# Gate_Driver_HV.net
KiCad netlist of a schematic drawn in Altium Designer
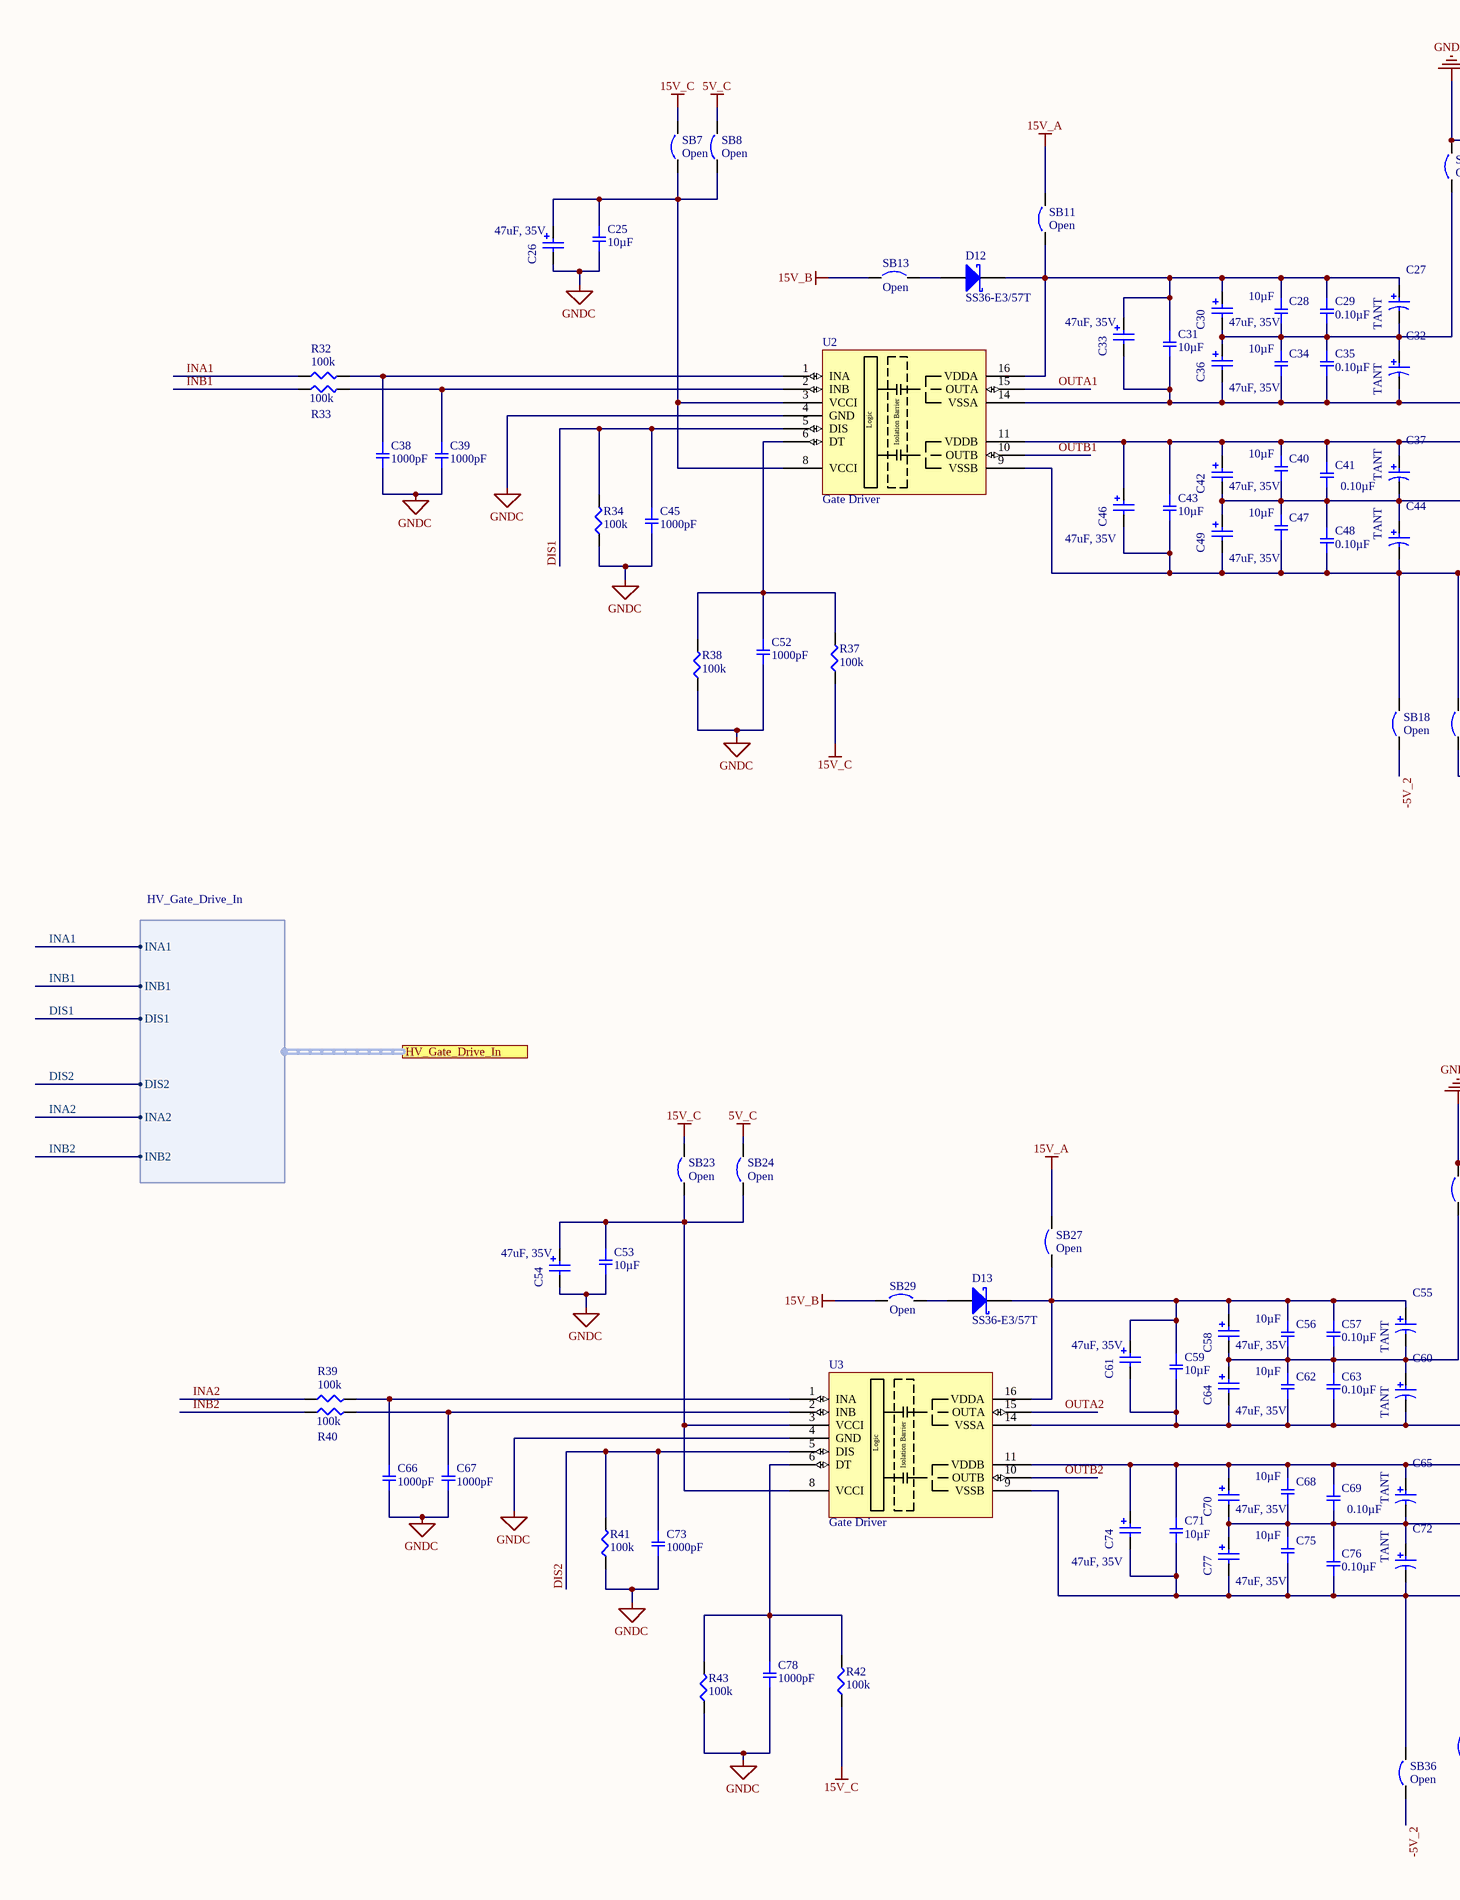
[diagram p0: Gate Driver HV.SchDoc, left]
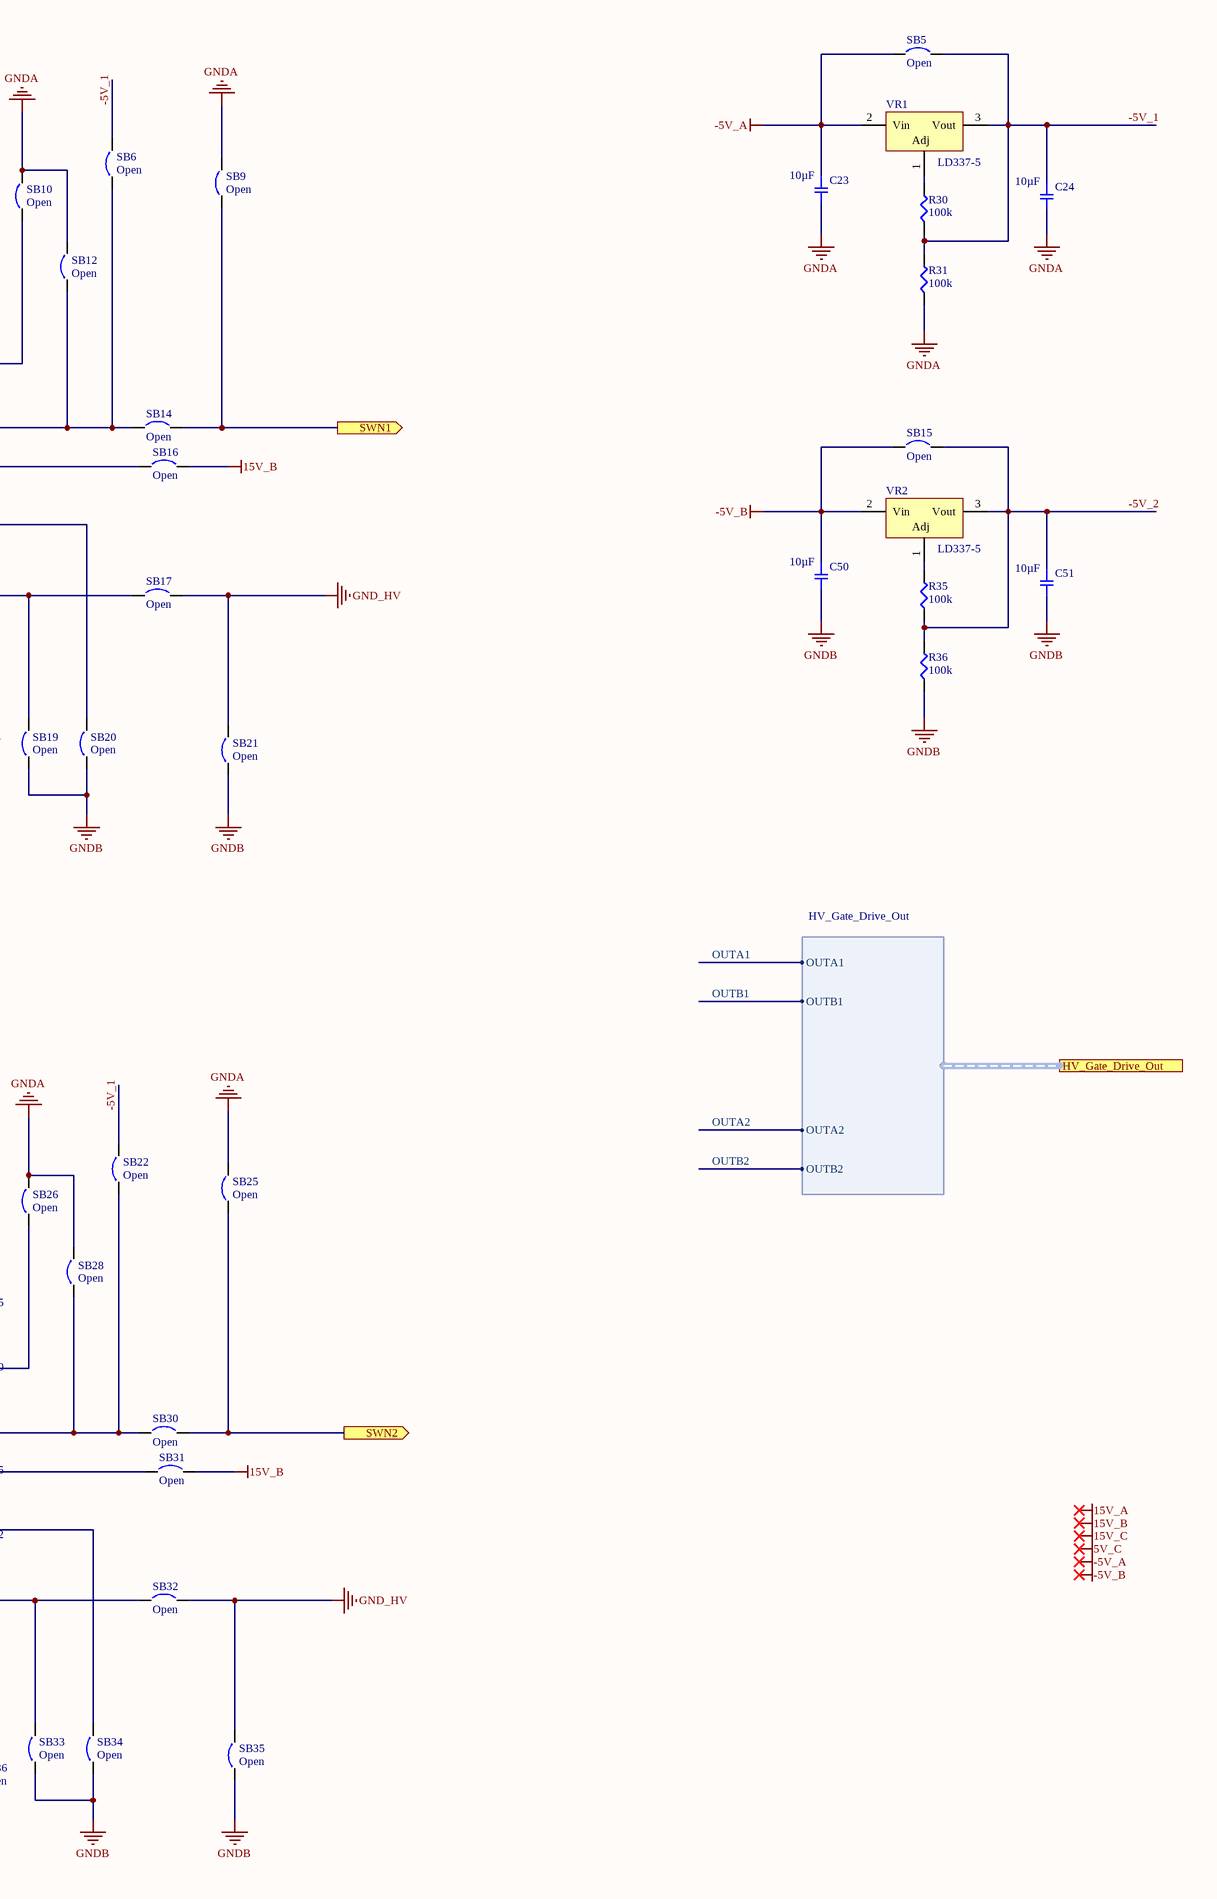
[diagram p1: Gate Driver HV.SchDoc, right]

(export (version "E")
  (design (tool "Eeschema 10.0.6"))
  (components
    (comp (ref "C23")
      (value "10µF")
      (footprint "SMD-1206C")
      (description "CAP CER 10UF 10V X7R 1206")
      (fields
        (field (name "DIGI-KEY PART NUMBER") "490-5848-1-ND")
        (field (name "PART NUMBER") "GCJ31CR71A106KA13L")
      )
      (libsource (lib "capacitor_murata_1206") (part "GCJ31CR71A106KA13L"))
    )
    (comp (ref "C24")
      (value "10µF")
      (footprint "SMD-1206C")
      (description "CAP CER 10UF 10V X7R 1206")
      (fields
        (field (name "DIGI-KEY PART NUMBER") "490-5848-1-ND")
        (field (name "PART NUMBER") "GCJ31CR71A106KA13L")
      )
      (libsource (lib "capacitor_murata_1206") (part "GCJ31CR71A106KA13L"))
    )
    (comp (ref "C25")
      (value "10µF")
      (footprint "SMD-1206C")
      (description "CAP CER 10UF 10V X7R 1206")
      (fields
        (field (name "DIGI-KEY PART NUMBER") "490-5848-1-ND")
        (field (name "PART NUMBER") "GCJ31CR71A106KA13L")
      )
      (libsource (lib "capacitor_murata_1206") (part "GCJ31CR71A106KA13L"))
    )
    (comp (ref "C26")
      (value "47uF, 35V")
      (footprint "WCAP-ASLL_6.3x5.5")
      (description "WCAP-ASLL SMT Aluminum Electrolytic Capacitors, D6.3mm x L5.5mm, 47uF, +/-20%, 35VDC")
      (fields (field (name "PART NUMBER") "865060543005") (field (name "PUBLISHER") "Wurth Elektronik"))
      (libsource (lib "Altium_WCAP-ASLL_SMD") (part "865060543005"))
    )
    (comp (ref "C27")
      (value "TANT")
      (footprint "KEMT-T491-D_L")
      (description "Tantalum Capacitor, 10 uF, +/- 10%, 35 V, -55 to 125 degC, 2-Pin SMD, RoHS, Tape and Reel")
      (fields (field (name "MANUFACTURER") "Kemet") (field (name "TOLERANCE") "20%"))
      (libsource (lib "Altium Content Vault") (part "CAP-P-2"))
    )
    (comp (ref "C28")
      (value "10µF")
      (footprint "SMD-1206C")
      (description "CAP CER 10UF 10V X7R 1206")
      (fields
        (field (name "DIGI-KEY PART NUMBER") "490-5848-1-ND")
        (field (name "PART NUMBER") "GCJ31CR71A106KA13L")
      )
      (libsource (lib "capacitor_murata_1206") (part "GCJ31CR71A106KA13L"))
    )
    (comp (ref "C29")
      (value "0.10µF")
      (footprint "SMD-1206C")
      (description "CAP CER 0.1UF 250V X7R 1206")
      (fields
        (field (name "DIGI-KEY PART NUMBER") "490-12647-1-ND")
        (field (name "PART NUMBER") "GCJ31CR72E104KXJ3L")
      )
      (libsource (lib "capacitor_murata_1206") (part "GCJ31CR72E104KXJ3L"))
    )
    (comp (ref "C30")
      (value "47uF, 35V")
      (footprint "WCAP-ASLL_6.3x5.5")
      (description "WCAP-ASLL SMT Aluminum Electrolytic Capacitors, D6.3mm x L5.5mm, 47uF, +/-20%, 35VDC")
      (fields (field (name "PART NUMBER") "865060543005") (field (name "PUBLISHER") "Wurth Elektronik"))
      (libsource (lib "Altium_WCAP-ASLL_SMD") (part "865060543005"))
    )
    (comp (ref "C31")
      (value "10µF")
      (footprint "SMD-1206C")
      (description "CAP CER 10UF 10V X7R 1206")
      (fields
        (field (name "DIGI-KEY PART NUMBER") "490-5848-1-ND")
        (field (name "PART NUMBER") "GCJ31CR71A106KA13L")
      )
      (libsource (lib "capacitor_murata_1206") (part "GCJ31CR71A106KA13L"))
    )
    (comp (ref "C32")
      (value "TANT")
      (footprint "KEMT-T491-D_L")
      (description "Tantalum Capacitor, 10 uF, +/- 10%, 35 V, -55 to 125 degC, 2-Pin SMD, RoHS, Tape and Reel")
      (fields (field (name "MANUFACTURER") "Kemet") (field (name "TOLERANCE") "20%"))
      (libsource (lib "Altium Content Vault") (part "CAP-P-2"))
    )
    (comp (ref "C33")
      (value "47uF, 35V")
      (footprint "WCAP-ASLL_6.3x5.5")
      (description "WCAP-ASLL SMT Aluminum Electrolytic Capacitors, D6.3mm x L5.5mm, 47uF, +/-20%, 35VDC")
      (fields (field (name "PART NUMBER") "865060543005") (field (name "PUBLISHER") "Wurth Elektronik"))
      (libsource (lib "Altium_WCAP-ASLL_SMD") (part "865060543005"))
    )
    (comp (ref "C34")
      (value "10µF")
      (footprint "SMD-1206C")
      (description "CAP CER 10UF 10V X7R 1206")
      (fields
        (field (name "DIGI-KEY PART NUMBER") "490-5848-1-ND")
        (field (name "PART NUMBER") "GCJ31CR71A106KA13L")
      )
      (libsource (lib "capacitor_murata_1206") (part "GCJ31CR71A106KA13L"))
    )
    (comp (ref "C35")
      (value "0.10µF")
      (footprint "SMD-1206C")
      (description "CAP CER 0.1UF 250V X7R 1206")
      (fields
        (field (name "DIGI-KEY PART NUMBER") "490-12647-1-ND")
        (field (name "PART NUMBER") "GCJ31CR72E104KXJ3L")
      )
      (libsource (lib "capacitor_murata_1206") (part "GCJ31CR72E104KXJ3L"))
    )
    (comp (ref "C36")
      (value "47uF, 35V")
      (footprint "WCAP-ASLL_6.3x5.5")
      (description "WCAP-ASLL SMT Aluminum Electrolytic Capacitors, D6.3mm x L5.5mm, 47uF, +/-20%, 35VDC")
      (fields (field (name "PART NUMBER") "865060543005") (field (name "PUBLISHER") "Wurth Elektronik"))
      (libsource (lib "Altium_WCAP-ASLL_SMD") (part "865060543005"))
    )
    (comp (ref "C37")
      (value "TANT")
      (footprint "KEMT-T491-D_L")
      (description "Tantalum Capacitor, 10 uF, +/- 10%, 35 V, -55 to 125 degC, 2-Pin SMD, RoHS, Tape and Reel")
      (fields (field (name "MANUFACTURER") "Kemet") (field (name "TOLERANCE") "20%"))
      (libsource (lib "Altium Content Vault") (part "CAP-P-2"))
    )
    (comp (ref "C38")
      (value "1000pF")
      (footprint "SMD-0805C")
      (description "CAP CER 1000PF 100V X7R 0805")
      (fields
        (field (name "DIGI-KEY PART NUMBER") "490-5818-1-ND")
        (field (name "PART NUMBER") "GCJ216R72A102KA01D")
      )
      (libsource (lib "capacitor_murata_0805") (part "GCJ216R72A102KA01D"))
    )
    (comp (ref "C39")
      (value "1000pF")
      (footprint "SMD-0805C")
      (description "CAP CER 1000PF 100V X7R 0805")
      (fields
        (field (name "DIGI-KEY PART NUMBER") "490-5818-1-ND")
        (field (name "PART NUMBER") "GCJ216R72A102KA01D")
      )
      (libsource (lib "capacitor_murata_0805") (part "GCJ216R72A102KA01D"))
    )
    (comp (ref "C40")
      (value "10µF")
      (footprint "SMD-1206C")
      (description "CAP CER 10UF 10V X7R 1206")
      (fields
        (field (name "DIGI-KEY PART NUMBER") "490-5848-1-ND")
        (field (name "PART NUMBER") "GCJ31CR71A106KA13L")
      )
      (libsource (lib "capacitor_murata_1206") (part "GCJ31CR71A106KA13L"))
    )
    (comp (ref "C41")
      (value "0.10µF")
      (footprint "SMD-1206C")
      (description "CAP CER 0.1UF 250V X7R 1206")
      (fields
        (field (name "DIGI-KEY PART NUMBER") "490-12647-1-ND")
        (field (name "PART NUMBER") "GCJ31CR72E104KXJ3L")
      )
      (libsource (lib "capacitor_murata_1206") (part "GCJ31CR72E104KXJ3L"))
    )
    (comp (ref "C42")
      (value "47uF, 35V")
      (footprint "WCAP-ASLL_6.3x5.5")
      (description "WCAP-ASLL SMT Aluminum Electrolytic Capacitors, D6.3mm x L5.5mm, 47uF, +/-20%, 35VDC")
      (fields (field (name "PART NUMBER") "865060543005") (field (name "PUBLISHER") "Wurth Elektronik"))
      (libsource (lib "Altium_WCAP-ASLL_SMD") (part "865060543005"))
    )
    (comp (ref "C43")
      (value "10µF")
      (footprint "SMD-1206C")
      (description "CAP CER 10UF 10V X7R 1206")
      (fields
        (field (name "DIGI-KEY PART NUMBER") "490-5848-1-ND")
        (field (name "PART NUMBER") "GCJ31CR71A106KA13L")
      )
      (libsource (lib "capacitor_murata_1206") (part "GCJ31CR71A106KA13L"))
    )
    (comp (ref "C44")
      (value "TANT")
      (footprint "KEMT-T491-D_L")
      (description "Tantalum Capacitor, 10 uF, +/- 10%, 35 V, -55 to 125 degC, 2-Pin SMD, RoHS, Tape and Reel")
      (fields (field (name "MANUFACTURER") "Kemet") (field (name "TOLERANCE") "20%"))
      (libsource (lib "Altium Content Vault") (part "CAP-P-2"))
    )
    (comp (ref "C45")
      (value "1000pF")
      (footprint "SMD-0805C")
      (description "CAP CER 1000PF 100V X7R 0805")
      (fields
        (field (name "DIGI-KEY PART NUMBER") "490-5818-1-ND")
        (field (name "PART NUMBER") "GCJ216R72A102KA01D")
      )
      (libsource (lib "capacitor_murata_0805") (part "GCJ216R72A102KA01D"))
    )
    (comp (ref "C46")
      (value "47uF, 35V")
      (footprint "WCAP-ASLL_6.3x5.5")
      (description "WCAP-ASLL SMT Aluminum Electrolytic Capacitors, D6.3mm x L5.5mm, 47uF, +/-20%, 35VDC")
      (fields (field (name "PART NUMBER") "865060543005") (field (name "PUBLISHER") "Wurth Elektronik"))
      (libsource (lib "Altium_WCAP-ASLL_SMD") (part "865060543005"))
    )
    (comp (ref "C47")
      (value "10µF")
      (footprint "SMD-1206C")
      (description "CAP CER 10UF 10V X7R 1206")
      (fields
        (field (name "DIGI-KEY PART NUMBER") "490-5848-1-ND")
        (field (name "PART NUMBER") "GCJ31CR71A106KA13L")
      )
      (libsource (lib "capacitor_murata_1206") (part "GCJ31CR71A106KA13L"))
    )
    (comp (ref "C48")
      (value "0.10µF")
      (footprint "SMD-1206C")
      (description "CAP CER 0.1UF 250V X7R 1206")
      (fields
        (field (name "DIGI-KEY PART NUMBER") "490-12647-1-ND")
        (field (name "PART NUMBER") "GCJ31CR72E104KXJ3L")
      )
      (libsource (lib "capacitor_murata_1206") (part "GCJ31CR72E104KXJ3L"))
    )
    (comp (ref "C49")
      (value "47uF, 35V")
      (footprint "WCAP-ASLL_6.3x5.5")
      (description "WCAP-ASLL SMT Aluminum Electrolytic Capacitors, D6.3mm x L5.5mm, 47uF, +/-20%, 35VDC")
      (fields (field (name "PART NUMBER") "865060543005") (field (name "PUBLISHER") "Wurth Elektronik"))
      (libsource (lib "Altium_WCAP-ASLL_SMD") (part "865060543005"))
    )
    (comp (ref "C50")
      (value "10µF")
      (footprint "SMD-1206C")
      (description "CAP CER 10UF 10V X7R 1206")
      (fields
        (field (name "DIGI-KEY PART NUMBER") "490-5848-1-ND")
        (field (name "PART NUMBER") "GCJ31CR71A106KA13L")
      )
      (libsource (lib "capacitor_murata_1206") (part "GCJ31CR71A106KA13L"))
    )
    (comp (ref "C51")
      (value "10µF")
      (footprint "SMD-1206C")
      (description "CAP CER 10UF 10V X7R 1206")
      (fields
        (field (name "DIGI-KEY PART NUMBER") "490-5848-1-ND")
        (field (name "PART NUMBER") "GCJ31CR71A106KA13L")
      )
      (libsource (lib "capacitor_murata_1206") (part "GCJ31CR71A106KA13L"))
    )
    (comp (ref "C52")
      (value "1000pF")
      (footprint "SMD-0805C")
      (description "CAP CER 1000PF 100V X7R 0805")
      (fields
        (field (name "DIGI-KEY PART NUMBER") "490-5818-1-ND")
        (field (name "PART NUMBER") "GCJ216R72A102KA01D")
      )
      (libsource (lib "capacitor_murata_0805") (part "GCJ216R72A102KA01D"))
    )
    (comp (ref "C53")
      (value "10µF")
      (footprint "SMD-1206C")
      (description "CAP CER 10UF 10V X7R 1206")
      (fields
        (field (name "DIGI-KEY PART NUMBER") "490-5848-1-ND")
        (field (name "PART NUMBER") "GCJ31CR71A106KA13L")
      )
      (libsource (lib "capacitor_murata_1206") (part "GCJ31CR71A106KA13L"))
    )
    (comp (ref "C54")
      (value "47uF, 35V")
      (footprint "WCAP-ASLL_6.3x5.5")
      (description "WCAP-ASLL SMT Aluminum Electrolytic Capacitors, D6.3mm x L5.5mm, 47uF, +/-20%, 35VDC")
      (fields (field (name "PART NUMBER") "865060543005") (field (name "PUBLISHER") "Wurth Elektronik"))
      (libsource (lib "Altium_WCAP-ASLL_SMD") (part "865060543005"))
    )
    (comp (ref "C55")
      (value "TANT")
      (footprint "KEMT-T491-D_L")
      (description "Tantalum Capacitor, 10 uF, +/- 10%, 35 V, -55 to 125 degC, 2-Pin SMD, RoHS, Tape and Reel")
      (fields (field (name "MANUFACTURER") "Kemet") (field (name "TOLERANCE") "20%"))
      (libsource (lib "Altium Content Vault") (part "CAP-P-2"))
    )
    (comp (ref "C56")
      (value "10µF")
      (footprint "SMD-1206C")
      (description "CAP CER 10UF 10V X7R 1206")
      (fields
        (field (name "DIGI-KEY PART NUMBER") "490-5848-1-ND")
        (field (name "PART NUMBER") "GCJ31CR71A106KA13L")
      )
      (libsource (lib "capacitor_murata_1206") (part "GCJ31CR71A106KA13L"))
    )
    (comp (ref "C57")
      (value "0.10µF")
      (footprint "SMD-1206C")
      (description "CAP CER 0.1UF 250V X7R 1206")
      (fields
        (field (name "DIGI-KEY PART NUMBER") "490-12647-1-ND")
        (field (name "PART NUMBER") "GCJ31CR72E104KXJ3L")
      )
      (libsource (lib "capacitor_murata_1206") (part "GCJ31CR72E104KXJ3L"))
    )
    (comp (ref "C58")
      (value "47uF, 35V")
      (footprint "WCAP-ASLL_6.3x5.5")
      (description "WCAP-ASLL SMT Aluminum Electrolytic Capacitors, D6.3mm x L5.5mm, 47uF, +/-20%, 35VDC")
      (fields (field (name "PART NUMBER") "865060543005") (field (name "PUBLISHER") "Wurth Elektronik"))
      (libsource (lib "Altium_WCAP-ASLL_SMD") (part "865060543005"))
    )
    (comp (ref "C59")
      (value "10µF")
      (footprint "SMD-1206C")
      (description "CAP CER 10UF 10V X7R 1206")
      (fields
        (field (name "DIGI-KEY PART NUMBER") "490-5848-1-ND")
        (field (name "PART NUMBER") "GCJ31CR71A106KA13L")
      )
      (libsource (lib "capacitor_murata_1206") (part "GCJ31CR71A106KA13L"))
    )
    (comp (ref "C60")
      (value "TANT")
      (footprint "KEMT-T491-D_L")
      (description "Tantalum Capacitor, 10 uF, +/- 10%, 35 V, -55 to 125 degC, 2-Pin SMD, RoHS, Tape and Reel")
      (fields (field (name "MANUFACTURER") "Kemet") (field (name "TOLERANCE") "20%"))
      (libsource (lib "Altium Content Vault") (part "CAP-P-2"))
    )
    (comp (ref "C61")
      (value "47uF, 35V")
      (footprint "WCAP-ASLL_6.3x5.5")
      (description "WCAP-ASLL SMT Aluminum Electrolytic Capacitors, D6.3mm x L5.5mm, 47uF, +/-20%, 35VDC")
      (fields (field (name "PART NUMBER") "865060543005") (field (name "PUBLISHER") "Wurth Elektronik"))
      (libsource (lib "Altium_WCAP-ASLL_SMD") (part "865060543005"))
    )
    (comp (ref "C62")
      (value "10µF")
      (footprint "SMD-1206C")
      (description "CAP CER 10UF 10V X7R 1206")
      (fields
        (field (name "DIGI-KEY PART NUMBER") "490-5848-1-ND")
        (field (name "PART NUMBER") "GCJ31CR71A106KA13L")
      )
      (libsource (lib "capacitor_murata_1206") (part "GCJ31CR71A106KA13L"))
    )
    (comp (ref "C63")
      (value "0.10µF")
      (footprint "SMD-1206C")
      (description "CAP CER 0.1UF 250V X7R 1206")
      (fields
        (field (name "DIGI-KEY PART NUMBER") "490-12647-1-ND")
        (field (name "PART NUMBER") "GCJ31CR72E104KXJ3L")
      )
      (libsource (lib "capacitor_murata_1206") (part "GCJ31CR72E104KXJ3L"))
    )
    (comp (ref "C64")
      (value "47uF, 35V")
      (footprint "WCAP-ASLL_6.3x5.5")
      (description "WCAP-ASLL SMT Aluminum Electrolytic Capacitors, D6.3mm x L5.5mm, 47uF, +/-20%, 35VDC")
      (fields (field (name "PART NUMBER") "865060543005") (field (name "PUBLISHER") "Wurth Elektronik"))
      (libsource (lib "Altium_WCAP-ASLL_SMD") (part "865060543005"))
    )
    (comp (ref "C65")
      (value "TANT")
      (footprint "KEMT-T491-D_L")
      (description "Tantalum Capacitor, 10 uF, +/- 10%, 35 V, -55 to 125 degC, 2-Pin SMD, RoHS, Tape and Reel")
      (fields (field (name "MANUFACTURER") "Kemet") (field (name "TOLERANCE") "20%"))
      (libsource (lib "Altium Content Vault") (part "CAP-P-2"))
    )
    (comp (ref "C66")
      (value "1000pF")
      (footprint "SMD-0805C")
      (description "CAP CER 1000PF 100V X7R 0805")
      (fields
        (field (name "DIGI-KEY PART NUMBER") "490-5818-1-ND")
        (field (name "PART NUMBER") "GCJ216R72A102KA01D")
      )
      (libsource (lib "capacitor_murata_0805") (part "GCJ216R72A102KA01D"))
    )
    (comp (ref "C67")
      (value "1000pF")
      (footprint "SMD-0805C")
      (description "CAP CER 1000PF 100V X7R 0805")
      (fields
        (field (name "DIGI-KEY PART NUMBER") "490-5818-1-ND")
        (field (name "PART NUMBER") "GCJ216R72A102KA01D")
      )
      (libsource (lib "capacitor_murata_0805") (part "GCJ216R72A102KA01D"))
    )
    (comp (ref "C68")
      (value "10µF")
      (footprint "SMD-1206C")
      (description "CAP CER 10UF 10V X7R 1206")
      (fields
        (field (name "DIGI-KEY PART NUMBER") "490-5848-1-ND")
        (field (name "PART NUMBER") "GCJ31CR71A106KA13L")
      )
      (libsource (lib "capacitor_murata_1206") (part "GCJ31CR71A106KA13L"))
    )
    (comp (ref "C69")
      (value "0.10µF")
      (footprint "SMD-1206C")
      (description "CAP CER 0.1UF 250V X7R 1206")
      (fields
        (field (name "DIGI-KEY PART NUMBER") "490-12647-1-ND")
        (field (name "PART NUMBER") "GCJ31CR72E104KXJ3L")
      )
      (libsource (lib "capacitor_murata_1206") (part "GCJ31CR72E104KXJ3L"))
    )
    (comp (ref "C70")
      (value "47uF, 35V")
      (footprint "WCAP-ASLL_6.3x5.5")
      (description "WCAP-ASLL SMT Aluminum Electrolytic Capacitors, D6.3mm x L5.5mm, 47uF, +/-20%, 35VDC")
      (fields (field (name "PART NUMBER") "865060543005") (field (name "PUBLISHER") "Wurth Elektronik"))
      (libsource (lib "Altium_WCAP-ASLL_SMD") (part "865060543005"))
    )
    (comp (ref "C71")
      (value "10µF")
      (footprint "SMD-1206C")
      (description "CAP CER 10UF 10V X7R 1206")
      (fields
        (field (name "DIGI-KEY PART NUMBER") "490-5848-1-ND")
        (field (name "PART NUMBER") "GCJ31CR71A106KA13L")
      )
      (libsource (lib "capacitor_murata_1206") (part "GCJ31CR71A106KA13L"))
    )
    (comp (ref "C72")
      (value "TANT")
      (footprint "KEMT-T491-D_L")
      (description "Tantalum Capacitor, 10 uF, +/- 10%, 35 V, -55 to 125 degC, 2-Pin SMD, RoHS, Tape and Reel")
      (fields (field (name "MANUFACTURER") "Kemet") (field (name "TOLERANCE") "20%"))
      (libsource (lib "Altium Content Vault") (part "CAP-P-2"))
    )
    (comp (ref "C73")
      (value "1000pF")
      (footprint "SMD-0805C")
      (description "CAP CER 1000PF 100V X7R 0805")
      (fields
        (field (name "DIGI-KEY PART NUMBER") "490-5818-1-ND")
        (field (name "PART NUMBER") "GCJ216R72A102KA01D")
      )
      (libsource (lib "capacitor_murata_0805") (part "GCJ216R72A102KA01D"))
    )
    (comp (ref "C74")
      (value "47uF, 35V")
      (footprint "WCAP-ASLL_6.3x5.5")
      (description "WCAP-ASLL SMT Aluminum Electrolytic Capacitors, D6.3mm x L5.5mm, 47uF, +/-20%, 35VDC")
      (fields (field (name "PART NUMBER") "865060543005") (field (name "PUBLISHER") "Wurth Elektronik"))
      (libsource (lib "Altium_WCAP-ASLL_SMD") (part "865060543005"))
    )
    (comp (ref "C75")
      (value "10µF")
      (footprint "SMD-1206C")
      (description "CAP CER 10UF 10V X7R 1206")
      (fields
        (field (name "DIGI-KEY PART NUMBER") "490-5848-1-ND")
        (field (name "PART NUMBER") "GCJ31CR71A106KA13L")
      )
      (libsource (lib "capacitor_murata_1206") (part "GCJ31CR71A106KA13L"))
    )
    (comp (ref "C76")
      (value "0.10µF")
      (footprint "SMD-1206C")
      (description "CAP CER 0.1UF 250V X7R 1206")
      (fields
        (field (name "DIGI-KEY PART NUMBER") "490-12647-1-ND")
        (field (name "PART NUMBER") "GCJ31CR72E104KXJ3L")
      )
      (libsource (lib "capacitor_murata_1206") (part "GCJ31CR72E104KXJ3L"))
    )
    (comp (ref "C77")
      (value "47uF, 35V")
      (footprint "WCAP-ASLL_6.3x5.5")
      (description "WCAP-ASLL SMT Aluminum Electrolytic Capacitors, D6.3mm x L5.5mm, 47uF, +/-20%, 35VDC")
      (fields (field (name "PART NUMBER") "865060543005") (field (name "PUBLISHER") "Wurth Elektronik"))
      (libsource (lib "Altium_WCAP-ASLL_SMD") (part "865060543005"))
    )
    (comp (ref "C78")
      (value "1000pF")
      (footprint "SMD-0805C")
      (description "CAP CER 1000PF 100V X7R 0805")
      (fields
        (field (name "DIGI-KEY PART NUMBER") "490-5818-1-ND")
        (field (name "PART NUMBER") "GCJ216R72A102KA01D")
      )
      (libsource (lib "capacitor_murata_0805") (part "GCJ216R72A102KA01D"))
    )
    (comp (ref "D12")
      (value "SS36-E3/57T")
      (footprint "VISH-DO-214AB-2_V")
      (fields (field (name "MANUFACTURER") "Vishay"))
      (libsource (lib "Altium Content Vault") (part "DSKY-AK-2"))
    )
    (comp (ref "D13")
      (value "SS36-E3/57T")
      (footprint "VISH-DO-214AB-2_V")
      (fields (field (name "MANUFACTURER") "Vishay"))
      (libsource (lib "Altium Content Vault") (part "DSKY-AK-2"))
    )
    (comp (ref "R30")
      (value "100k")
      (footprint "SMD-0805-RES")
      (description "RES SMD 100K OHM 1% 1/8W 0805")
      (fields
        (field (name "PART NUMBER") "ERJ-6ENF1003V")
        (field (name "DIGI-KEY PART NUMBER") "P100KCCT-ND")
      )
      (libsource (lib "Panasonic_ERJ_0805") (part "ERJ-6ENF1003V"))
    )
    (comp (ref "R31")
      (value "100k")
      (footprint "SMD-0805-RES")
      (description "RES SMD 100K OHM 1% 1/8W 0805")
      (fields
        (field (name "PART NUMBER") "ERJ-6ENF1003V")
        (field (name "DIGI-KEY PART NUMBER") "P100KCCT-ND")
      )
      (libsource (lib "Panasonic_ERJ_0805") (part "ERJ-6ENF1003V"))
    )
    (comp (ref "R32")
      (value "100k")
      (footprint "SMD-0805-RES")
      (description "RES SMD 100K OHM 1% 1/8W 0805")
      (fields
        (field (name "PART NUMBER") "ERJ-6ENF1003V")
        (field (name "DIGI-KEY PART NUMBER") "P100KCCT-ND")
      )
      (libsource (lib "Panasonic_ERJ_0805") (part "ERJ-6ENF1003V"))
    )
    (comp (ref "R33")
      (value "100k")
      (footprint "SMD-0805-RES")
      (description "RES SMD 100K OHM 1% 1/8W 0805")
      (fields
        (field (name "PART NUMBER") "ERJ-6ENF1003V")
        (field (name "DIGI-KEY PART NUMBER") "P100KCCT-ND")
      )
      (libsource (lib "Panasonic_ERJ_0805") (part "ERJ-6ENF1003V"))
    )
    (comp (ref "R34")
      (value "100k")
      (footprint "SMD-0805-RES")
      (description "RES SMD 100K OHM 1% 1/8W 0805")
      (fields
        (field (name "PART NUMBER") "ERJ-6ENF1003V")
        (field (name "DIGI-KEY PART NUMBER") "P100KCCT-ND")
      )
      (libsource (lib "Panasonic_ERJ_0805") (part "ERJ-6ENF1003V"))
    )
    (comp (ref "R35")
      (value "100k")
      (footprint "SMD-0805-RES")
      (description "RES SMD 100K OHM 1% 1/8W 0805")
      (fields
        (field (name "PART NUMBER") "ERJ-6ENF1003V")
        (field (name "DIGI-KEY PART NUMBER") "P100KCCT-ND")
      )
      (libsource (lib "Panasonic_ERJ_0805") (part "ERJ-6ENF1003V"))
    )
    (comp (ref "R36")
      (value "100k")
      (footprint "SMD-0805-RES")
      (description "RES SMD 100K OHM 1% 1/8W 0805")
      (fields
        (field (name "PART NUMBER") "ERJ-6ENF1003V")
        (field (name "DIGI-KEY PART NUMBER") "P100KCCT-ND")
      )
      (libsource (lib "Panasonic_ERJ_0805") (part "ERJ-6ENF1003V"))
    )
    (comp (ref "R37")
      (value "100k")
      (footprint "SMD-0805-RES")
      (description "RES SMD 100K OHM 1% 1/8W 0805")
      (fields
        (field (name "PART NUMBER") "ERJ-6ENF1003V")
        (field (name "DIGI-KEY PART NUMBER") "P100KCCT-ND")
      )
      (libsource (lib "Panasonic_ERJ_0805") (part "ERJ-6ENF1003V"))
    )
    (comp (ref "R38")
      (value "100k")
      (footprint "SMD-0805-RES")
      (description "RES SMD 100K OHM 1% 1/8W 0805")
      (fields
        (field (name "PART NUMBER") "ERJ-6ENF1003V")
        (field (name "DIGI-KEY PART NUMBER") "P100KCCT-ND")
      )
      (libsource (lib "Panasonic_ERJ_0805") (part "ERJ-6ENF1003V"))
    )
    (comp (ref "R39")
      (value "100k")
      (footprint "SMD-0805-RES")
      (description "RES SMD 100K OHM 1% 1/8W 0805")
      (fields
        (field (name "PART NUMBER") "ERJ-6ENF1003V")
        (field (name "DIGI-KEY PART NUMBER") "P100KCCT-ND")
      )
      (libsource (lib "Panasonic_ERJ_0805") (part "ERJ-6ENF1003V"))
    )
    (comp (ref "R40")
      (value "100k")
      (footprint "SMD-0805-RES")
      (description "RES SMD 100K OHM 1% 1/8W 0805")
      (fields
        (field (name "PART NUMBER") "ERJ-6ENF1003V")
        (field (name "DIGI-KEY PART NUMBER") "P100KCCT-ND")
      )
      (libsource (lib "Panasonic_ERJ_0805") (part "ERJ-6ENF1003V"))
    )
    (comp (ref "R41")
      (value "100k")
      (footprint "SMD-0805-RES")
      (description "RES SMD 100K OHM 1% 1/8W 0805")
      (fields
        (field (name "PART NUMBER") "ERJ-6ENF1003V")
        (field (name "DIGI-KEY PART NUMBER") "P100KCCT-ND")
      )
      (libsource (lib "Panasonic_ERJ_0805") (part "ERJ-6ENF1003V"))
    )
    (comp (ref "R42")
      (value "100k")
      (footprint "SMD-0805-RES")
      (description "RES SMD 100K OHM 1% 1/8W 0805")
      (fields
        (field (name "PART NUMBER") "ERJ-6ENF1003V")
        (field (name "DIGI-KEY PART NUMBER") "P100KCCT-ND")
      )
      (libsource (lib "Panasonic_ERJ_0805") (part "ERJ-6ENF1003V"))
    )
    (comp (ref "R43")
      (value "100k")
      (footprint "SMD-0805-RES")
      (description "RES SMD 100K OHM 1% 1/8W 0805")
      (fields
        (field (name "PART NUMBER") "ERJ-6ENF1003V")
        (field (name "DIGI-KEY PART NUMBER") "P100KCCT-ND")
      )
      (libsource (lib "Panasonic_ERJ_0805") (part "ERJ-6ENF1003V"))
    )
    (comp (ref "SB5")
      (value "Open")
      (footprint "SB_0603")
      (description "Circuit Breaker")
      (fields (field (name "PUBLISHER") "Altium Limited"))
      (libsource (lib "Power Board UCC28951") (part "Solder Bridge"))
    )
    (comp (ref "SB6")
      (value "Open")
      (footprint "SB_0603")
      (description "Circuit Breaker")
      (fields (field (name "PUBLISHER") "Altium Limited"))
      (libsource (lib "Power Board UCC28951") (part "Solder Bridge"))
    )
    (comp (ref "SB7")
      (value "Open")
      (footprint "SB_0603")
      (description "Circuit Breaker")
      (fields (field (name "PUBLISHER") "Altium Limited"))
      (libsource (lib "Power Board UCC28951") (part "Solder Bridge"))
    )
    (comp (ref "SB8")
      (value "Open")
      (footprint "SB_0603")
      (description "Circuit Breaker")
      (fields (field (name "PUBLISHER") "Altium Limited"))
      (libsource (lib "Power Board UCC28951") (part "Solder Bridge"))
    )
    (comp (ref "SB9")
      (value "Open")
      (footprint "SB_0603")
      (description "Circuit Breaker")
      (fields (field (name "PUBLISHER") "Altium Limited"))
      (libsource (lib "Power Board UCC28951") (part "Solder Bridge"))
    )
    (comp (ref "SB10")
      (value "Open")
      (footprint "SB_0603")
      (description "Circuit Breaker")
      (fields (field (name "PUBLISHER") "Altium Limited"))
      (libsource (lib "Power Board UCC28951") (part "Solder Bridge"))
    )
    (comp (ref "SB11")
      (value "Open")
      (footprint "SB_0603")
      (description "Circuit Breaker")
      (fields (field (name "PUBLISHER") "Altium Limited"))
      (libsource (lib "Power Board UCC28951") (part "Solder Bridge"))
    )
    (comp (ref "SB12")
      (value "Open")
      (footprint "SB_0603")
      (description "Circuit Breaker")
      (fields (field (name "PUBLISHER") "Altium Limited"))
      (libsource (lib "Power Board UCC28951") (part "Solder Bridge"))
    )
    (comp (ref "SB13")
      (value "Open")
      (footprint "SB_0603")
      (description "Circuit Breaker")
      (fields (field (name "PUBLISHER") "Altium Limited"))
      (libsource (lib "Power Board UCC28951") (part "Solder Bridge"))
    )
    (comp (ref "SB14")
      (value "Open")
      (footprint "SB_0603")
      (description "Circuit Breaker")
      (fields (field (name "PUBLISHER") "Altium Limited"))
      (libsource (lib "Power Board UCC28951") (part "Solder Bridge"))
    )
    (comp (ref "SB15")
      (value "Open")
      (footprint "SB_0603")
      (description "Circuit Breaker")
      (fields (field (name "PUBLISHER") "Altium Limited"))
      (libsource (lib "Power Board UCC28951") (part "Solder Bridge"))
    )
    (comp (ref "SB16")
      (value "Open")
      (footprint "SB_0603")
      (description "Circuit Breaker")
      (fields (field (name "PUBLISHER") "Altium Limited"))
      (libsource (lib "Power Board UCC28951") (part "Solder Bridge"))
    )
    (comp (ref "SB17")
      (value "Open")
      (footprint "SB_0603")
      (description "Circuit Breaker")
      (fields (field (name "PUBLISHER") "Altium Limited"))
      (libsource (lib "Power Board UCC28951") (part "Solder Bridge"))
    )
    (comp (ref "SB18")
      (value "Open")
      (footprint "SB_0603")
      (description "Circuit Breaker")
      (fields (field (name "PUBLISHER") "Altium Limited"))
      (libsource (lib "Power Board UCC28951") (part "Solder Bridge"))
    )
    (comp (ref "SB19")
      (value "Open")
      (footprint "SB_0603")
      (description "Circuit Breaker")
      (fields (field (name "PUBLISHER") "Altium Limited"))
      (libsource (lib "Power Board UCC28951") (part "Solder Bridge"))
    )
    (comp (ref "SB20")
      (value "Open")
      (footprint "SB_0603")
      (description "Circuit Breaker")
      (fields (field (name "PUBLISHER") "Altium Limited"))
      (libsource (lib "Power Board UCC28951") (part "Solder Bridge"))
    )
    (comp (ref "SB21")
      (value "Open")
      (footprint "SB_0603")
      (description "Circuit Breaker")
      (fields (field (name "PUBLISHER") "Altium Limited"))
      (libsource (lib "Power Board UCC28951") (part "Solder Bridge"))
    )
    (comp (ref "SB22")
      (value "Open")
      (footprint "SB_0603")
      (description "Circuit Breaker")
      (fields (field (name "PUBLISHER") "Altium Limited"))
      (libsource (lib "Power Board UCC28951") (part "Solder Bridge"))
    )
    (comp (ref "SB23")
      (value "Open")
      (footprint "SB_0603")
      (description "Circuit Breaker")
      (fields (field (name "PUBLISHER") "Altium Limited"))
      (libsource (lib "Power Board UCC28951") (part "Solder Bridge"))
    )
    (comp (ref "SB24")
      (value "Open")
      (footprint "SB_0603")
      (description "Circuit Breaker")
      (fields (field (name "PUBLISHER") "Altium Limited"))
      (libsource (lib "Power Board UCC28951") (part "Solder Bridge"))
    )
    (comp (ref "SB25")
      (value "Open")
      (footprint "SB_0603")
      (description "Circuit Breaker")
      (fields (field (name "PUBLISHER") "Altium Limited"))
      (libsource (lib "Power Board UCC28951") (part "Solder Bridge"))
    )
    (comp (ref "SB26")
      (value "Open")
      (footprint "SB_0603")
      (description "Circuit Breaker")
      (fields (field (name "PUBLISHER") "Altium Limited"))
      (libsource (lib "Power Board UCC28951") (part "Solder Bridge"))
    )
    (comp (ref "SB27")
      (value "Open")
      (footprint "SB_0603")
      (description "Circuit Breaker")
      (fields (field (name "PUBLISHER") "Altium Limited"))
      (libsource (lib "Power Board UCC28951") (part "Solder Bridge"))
    )
    (comp (ref "SB28")
      (value "Open")
      (footprint "SB_0603")
      (description "Circuit Breaker")
      (fields (field (name "PUBLISHER") "Altium Limited"))
      (libsource (lib "Power Board UCC28951") (part "Solder Bridge"))
    )
    (comp (ref "SB29")
      (value "Open")
      (footprint "SB_0603")
      (description "Circuit Breaker")
      (fields (field (name "PUBLISHER") "Altium Limited"))
      (libsource (lib "Power Board UCC28951") (part "Solder Bridge"))
    )
    (comp (ref "SB30")
      (value "Open")
      (footprint "SB_0603")
      (description "Circuit Breaker")
      (fields (field (name "PUBLISHER") "Altium Limited"))
      (libsource (lib "Power Board UCC28951") (part "Solder Bridge"))
    )
    (comp (ref "SB31")
      (value "Open")
      (footprint "SB_0603")
      (description "Circuit Breaker")
      (fields (field (name "PUBLISHER") "Altium Limited"))
      (libsource (lib "Power Board UCC28951") (part "Solder Bridge"))
    )
    (comp (ref "SB32")
      (value "Open")
      (footprint "SB_0603")
      (description "Circuit Breaker")
      (fields (field (name "PUBLISHER") "Altium Limited"))
      (libsource (lib "Power Board UCC28951") (part "Solder Bridge"))
    )
    (comp (ref "SB33")
      (value "Open")
      (footprint "SB_0603")
      (description "Circuit Breaker")
      (fields (field (name "PUBLISHER") "Altium Limited"))
      (libsource (lib "Power Board UCC28951") (part "Solder Bridge"))
    )
    (comp (ref "SB34")
      (value "Open")
      (footprint "SB_0603")
      (description "Circuit Breaker")
      (fields (field (name "PUBLISHER") "Altium Limited"))
      (libsource (lib "Power Board UCC28951") (part "Solder Bridge"))
    )
    (comp (ref "SB35")
      (value "Open")
      (footprint "SB_0603")
      (description "Circuit Breaker")
      (fields (field (name "PUBLISHER") "Altium Limited"))
      (libsource (lib "Power Board UCC28951") (part "Solder Bridge"))
    )
    (comp (ref "SB36")
      (value "Open")
      (footprint "SB_0603")
      (description "Circuit Breaker")
      (fields (field (name "PUBLISHER") "Altium Limited"))
      (libsource (lib "Power Board UCC28951") (part "Solder Bridge"))
    )
    (comp (ref "U2")
      (value "Gate Driver")
      (footprint "SOIC127P1030X265_HS-17N")
      (libsource (lib "Power Board UCC28951") (part "Gate Driver"))
    )
    (comp (ref "U3")
      (value "Gate Driver")
      (footprint "SOIC127P1030X265_HS-17N")
      (libsource (lib "Power Board UCC28951") (part "Gate Driver"))
    )
    (comp (ref "VR1")
      (value "LD337-5")
      (footprint "SOT230P700X180-4N")
      (description "Voltage Regulator")
      (fields (field (name "PUBLISHER") "Altium Limited"))
      (libsource (lib "Power Board UCC28951") (part "LM337-Negative_Adj"))
    )
    (comp (ref "VR2")
      (value "LD337-5")
      (footprint "SOT230P700X180-4N")
      (description "Voltage Regulator")
      (fields (field (name "PUBLISHER") "Altium Limited"))
      (libsource (lib "Power Board UCC28951") (part "LM337-Negative_Adj"))
    )
  )
  (nets
    (net (code "3") (name "-5V_A") (class "Default")
      (node (ref "C23") (pin "1") (pinfunction "1_1") (pintype "passive"))
      (node (ref "SB5") (pin "1") (pinfunction "1_1") (pintype "passive"))
      (node (ref "VR1") (pin "2") (pinfunction "Vin_2") (pintype "passive"))
    )
    (net (code "4") (name "-5V_B") (class "Default")
      (node (ref "C50") (pin "1") (pinfunction "1_1") (pintype "passive"))
      (node (ref "SB15") (pin "1") (pinfunction "1_1") (pintype "passive"))
      (node (ref "VR2") (pin "2") (pinfunction "Vin_2") (pintype "passive"))
    )
    (net (code "5") (name "/-5V_1") (class "Default")
      (node (ref "C24") (pin "1") (pinfunction "1_1") (pintype "passive"))
      (node (ref "R30") (pin "1") (pinfunction "1_1") (pintype "passive"))
      (node (ref "R31") (pin "2") (pinfunction "2_2") (pintype "passive"))
      (node (ref "SB22") (pin "2") (pinfunction "2_2") (pintype "passive"))
      (node (ref "SB5") (pin "2") (pinfunction "2_2") (pintype "passive"))
      (node (ref "SB6") (pin "2") (pinfunction "2_2") (pintype "passive"))
      (node (ref "VR1") (pin "3") (pinfunction "Vout_3") (pintype "passive"))
    )
    (net (code "6") (name "/-5V_2") (class "Default")
      (node (ref "C51") (pin "1") (pinfunction "1_1") (pintype "passive"))
      (node (ref "R35") (pin "1") (pinfunction "1_1") (pintype "passive"))
      (node (ref "R36") (pin "2") (pinfunction "2_2") (pintype "passive"))
      (node (ref "SB15") (pin "2") (pinfunction "2_2") (pintype "passive"))
      (node (ref "SB18") (pin "1") (pinfunction "1_1") (pintype "passive"))
      (node (ref "SB36") (pin "1") (pinfunction "1_1") (pintype "passive"))
      (node (ref "VR2") (pin "3") (pinfunction "Vout_3") (pintype "passive"))
    )
    (net (code "7") (name "/DIS1") (class "Default")
      (node (ref "C45") (pin "1") (pinfunction "1_1") (pintype "passive"))
      (node (ref "R34") (pin "2") (pinfunction "2_2") (pintype "passive"))
      (node (ref "U2") (pin "5") (pinfunction "DIS_5") (pintype "bidirectional"))
    )
    (net (code "8") (name "/DIS2") (class "Default")
      (node (ref "C73") (pin "1") (pinfunction "1_1") (pintype "passive"))
      (node (ref "R41") (pin "2") (pinfunction "2_2") (pintype "passive"))
      (node (ref "U3") (pin "5") (pinfunction "DIS_5") (pintype "bidirectional"))
    )
    (net (code "9") (name "/INA1") (class "Default")
      (node (ref "R32") (pin "1") (pinfunction "1_1") (pintype "passive"))
    )
    (net (code "10") (name "/INA2") (class "Default")
      (node (ref "R39") (pin "1") (pinfunction "1_1") (pintype "passive"))
    )
    (net (code "11") (name "/INB1") (class "Default")
      (node (ref "R33") (pin "1") (pinfunction "1_1") (pintype "passive"))
    )
    (net (code "12") (name "/INB2") (class "Default")
      (node (ref "R40") (pin "1") (pinfunction "1_1") (pintype "passive"))
    )
    (net (code "13") (name "/OUTA1") (class "Default")
      (node (ref "U2") (pin "15") (pinfunction "OUTA_15") (pintype "bidirectional"))
    )
    (net (code "14") (name "/OUTA2") (class "Default")
      (node (ref "U3") (pin "15") (pinfunction "OUTA_15") (pintype "bidirectional"))
    )
    (net (code "15") (name "/OUTB1") (class "Default")
      (node (ref "U2") (pin "10") (pinfunction "OUTB_10") (pintype "bidirectional"))
    )
    (net (code "16") (name "/OUTB2") (class "Default")
      (node (ref "U3") (pin "10") (pinfunction "OUTB_10") (pintype "bidirectional"))
    )
    (net (code "17") (name "/SWN1") (class "Default")
      (node (ref "SB14") (pin "2") (pinfunction "2_2") (pintype "passive"))
      (node (ref "SB9") (pin "1") (pinfunction "1_1") (pintype "passive"))
    )
    (net (code "18") (name "/SWN2") (class "Default")
      (node (ref "SB25") (pin "1") (pinfunction "1_1") (pintype "passive"))
      (node (ref "SB30") (pin "2") (pinfunction "2_2") (pintype "passive"))
    )
    (net (code "21") (name "5V_C") (class "Default")
      (node (ref "SB24") (pin "2") (pinfunction "2_2") (pintype "passive"))
      (node (ref "SB8") (pin "2") (pinfunction "2_2") (pintype "passive"))
    )
    (net (code "22") (name "15V_A") (class "Default")
      (node (ref "SB11") (pin "2") (pinfunction "2_2") (pintype "passive"))
      (node (ref "SB27") (pin "2") (pinfunction "2_2") (pintype "passive"))
    )
    (net (code "23") (name "15V_B") (class "Default")
      (node (ref "SB13") (pin "1") (pinfunction "1_1") (pintype "passive"))
      (node (ref "SB16") (pin "2") (pinfunction "2_2") (pintype "passive"))
      (node (ref "SB29") (pin "1") (pinfunction "1_1") (pintype "passive"))
      (node (ref "SB31") (pin "2") (pinfunction "2_2") (pintype "passive"))
    )
    (net (code "24") (name "15V_C") (class "Default")
      (node (ref "R37") (pin "1") (pinfunction "1_1") (pintype "passive"))
      (node (ref "R42") (pin "1") (pinfunction "1_1") (pintype "passive"))
      (node (ref "SB23") (pin "2") (pinfunction "2_2") (pintype "passive"))
      (node (ref "SB7") (pin "2") (pinfunction "2_2") (pintype "passive"))
    )
    (net (code "25") (name "GNDA") (class "Default")
      (node (ref "C23") (pin "2") (pinfunction "2_2") (pintype "passive"))
      (node (ref "C24") (pin "2") (pinfunction "2_2") (pintype "passive"))
      (node (ref "R31") (pin "1") (pinfunction "1_1") (pintype "passive"))
      (node (ref "SB10") (pin "2") (pinfunction "2_2") (pintype "passive"))
      (node (ref "SB12") (pin "2") (pinfunction "2_2") (pintype "passive"))
      (node (ref "SB25") (pin "2") (pinfunction "2_2") (pintype "passive"))
      (node (ref "SB26") (pin "2") (pinfunction "2_2") (pintype "passive"))
      (node (ref "SB28") (pin "2") (pinfunction "2_2") (pintype "passive"))
      (node (ref "SB9") (pin "2") (pinfunction "2_2") (pintype "passive"))
    )
    (net (code "26") (name "GNDB") (class "Default")
      (node (ref "C50") (pin "2") (pinfunction "2_2") (pintype "passive"))
      (node (ref "C51") (pin "2") (pinfunction "2_2") (pintype "passive"))
      (node (ref "R36") (pin "1") (pinfunction "1_1") (pintype "passive"))
      (node (ref "SB19") (pin "1") (pinfunction "1_1") (pintype "passive"))
      (node (ref "SB20") (pin "1") (pinfunction "1_1") (pintype "passive"))
      (node (ref "SB21") (pin "1") (pinfunction "1_1") (pintype "passive"))
      (node (ref "SB33") (pin "1") (pinfunction "1_1") (pintype "passive"))
      (node (ref "SB34") (pin "1") (pinfunction "1_1") (pintype "passive"))
      (node (ref "SB35") (pin "1") (pinfunction "1_1") (pintype "passive"))
    )
    (net (code "27") (name "GNDC") (class "Default")
      (node (ref "C25") (pin "2") (pinfunction "2_2") (pintype "passive"))
      (node (ref "C26") (pin "1") (pinfunction "N_1") (pintype "passive"))
      (node (ref "C38") (pin "2") (pinfunction "2_2") (pintype "passive"))
      (node (ref "C39") (pin "2") (pinfunction "2_2") (pintype "passive"))
      (node (ref "C45") (pin "2") (pinfunction "2_2") (pintype "passive"))
      (node (ref "C52") (pin "2") (pinfunction "2_2") (pintype "passive"))
      (node (ref "C53") (pin "2") (pinfunction "2_2") (pintype "passive"))
      (node (ref "C54") (pin "1") (pinfunction "N_1") (pintype "passive"))
      (node (ref "C66") (pin "2") (pinfunction "2_2") (pintype "passive"))
      (node (ref "C67") (pin "2") (pinfunction "2_2") (pintype "passive"))
      (node (ref "C73") (pin "2") (pinfunction "2_2") (pintype "passive"))
      (node (ref "C78") (pin "2") (pinfunction "2_2") (pintype "passive"))
      (node (ref "R34") (pin "1") (pinfunction "1_1") (pintype "passive"))
      (node (ref "R38") (pin "1") (pinfunction "1_1") (pintype "passive"))
      (node (ref "R41") (pin "1") (pinfunction "1_1") (pintype "passive"))
      (node (ref "R43") (pin "1") (pinfunction "1_1") (pintype "passive"))
      (node (ref "U2") (pin "4") (pinfunction "GND_4") (pintype "power_in"))
      (node (ref "U3") (pin "4") (pinfunction "GND_4") (pintype "power_in"))
    )
    (net (code "28") (name "GND_HV") (class "Default")
      (node (ref "SB17") (pin "2") (pinfunction "2_2") (pintype "passive"))
      (node (ref "SB21") (pin "2") (pinfunction "2_2") (pintype "passive"))
      (node (ref "SB32") (pin "2") (pinfunction "2_2") (pintype "passive"))
      (node (ref "SB35") (pin "2") (pinfunction "2_2") (pintype "passive"))
    )
    (net (code "29") (name "Net-(C26-P)") (class "Default")
      (node (ref "C25") (pin "1") (pinfunction "1_1") (pintype "passive"))
      (node (ref "C26") (pin "2") (pinfunction "P_2") (pintype "passive"))
      (node (ref "SB7") (pin "1") (pinfunction "1_1") (pintype "passive"))
      (node (ref "SB8") (pin "1") (pinfunction "1_1") (pintype "passive"))
      (node (ref "U2") (pin "3") (pinfunction "VCCI_3") (pintype "power_in"))
      (node (ref "U2") (pin "8") (pinfunction "VCCI_8") (pintype "power_in"))
    )
    (net (code "30") (name "Net-(C30-N)") (class "Default")
      (node (ref "C27") (pin "2") (pinfunction "2_2") (pintype "passive"))
      (node (ref "C28") (pin "2") (pinfunction "2_2") (pintype "passive"))
      (node (ref "C29") (pin "2") (pinfunction "2_2") (pintype "passive"))
      (node (ref "C30") (pin "1") (pinfunction "N_1") (pintype "passive"))
      (node (ref "C32") (pin "1") (pinfunction "1_1") (pintype "passive"))
      (node (ref "C34") (pin "1") (pinfunction "1_1") (pintype "passive"))
      (node (ref "C35") (pin "1") (pinfunction "1_1") (pintype "passive"))
      (node (ref "C36") (pin "2") (pinfunction "P_2") (pintype "passive"))
      (node (ref "SB10") (pin "1") (pinfunction "1_1") (pintype "passive"))
    )
    (net (code "31") (name "Net-(C30-P)") (class "Default")
      (node (ref "C27") (pin "1") (pinfunction "1_1") (pintype "passive"))
      (node (ref "C28") (pin "1") (pinfunction "1_1") (pintype "passive"))
      (node (ref "C29") (pin "1") (pinfunction "1_1") (pintype "passive"))
      (node (ref "C30") (pin "2") (pinfunction "P_2") (pintype "passive"))
      (node (ref "C31") (pin "1") (pinfunction "1_1") (pintype "passive"))
      (node (ref "C33") (pin "2") (pinfunction "P_2") (pintype "passive"))
      (node (ref "D12") (pin "2") (pinfunction "K_2") (pintype "passive"))
      (node (ref "SB11") (pin "1") (pinfunction "1_1") (pintype "passive"))
      (node (ref "U2") (pin "16") (pinfunction "VDDA_16") (pintype "power_in"))
    )
    (net (code "32") (name "Net-(C33-N)") (class "Default")
      (node (ref "C31") (pin "2") (pinfunction "2_2") (pintype "passive"))
      (node (ref "C32") (pin "2") (pinfunction "2_2") (pintype "passive"))
      (node (ref "C33") (pin "1") (pinfunction "N_1") (pintype "passive"))
      (node (ref "C34") (pin "2") (pinfunction "2_2") (pintype "passive"))
      (node (ref "C35") (pin "2") (pinfunction "2_2") (pintype "passive"))
      (node (ref "C36") (pin "1") (pinfunction "N_1") (pintype "passive"))
      (node (ref "SB12") (pin "1") (pinfunction "1_1") (pintype "passive"))
      (node (ref "SB14") (pin "1") (pinfunction "1_1") (pintype "passive"))
      (node (ref "SB6") (pin "1") (pinfunction "1_1") (pintype "passive"))
      (node (ref "U2") (pin "14") (pinfunction "VSSA_14") (pintype "power_in"))
    )
    (net (code "33") (name "Net-(C42-N)") (class "Default")
      (node (ref "C37") (pin "2") (pinfunction "2_2") (pintype "passive"))
      (node (ref "C40") (pin "2") (pinfunction "2_2") (pintype "passive"))
      (node (ref "C41") (pin "2") (pinfunction "2_2") (pintype "passive"))
      (node (ref "C42") (pin "1") (pinfunction "N_1") (pintype "passive"))
      (node (ref "C44") (pin "1") (pinfunction "1_1") (pintype "passive"))
      (node (ref "C47") (pin "1") (pinfunction "1_1") (pintype "passive"))
      (node (ref "C48") (pin "1") (pinfunction "1_1") (pintype "passive"))
      (node (ref "C49") (pin "2") (pinfunction "P_2") (pintype "passive"))
      (node (ref "SB20") (pin "2") (pinfunction "2_2") (pintype "passive"))
    )
    (net (code "34") (name "Net-(C42-P)") (class "Default")
      (node (ref "C37") (pin "1") (pinfunction "1_1") (pintype "passive"))
      (node (ref "C40") (pin "1") (pinfunction "1_1") (pintype "passive"))
      (node (ref "C41") (pin "1") (pinfunction "1_1") (pintype "passive"))
      (node (ref "C42") (pin "2") (pinfunction "P_2") (pintype "passive"))
      (node (ref "C43") (pin "1") (pinfunction "1_1") (pintype "passive"))
      (node (ref "C46") (pin "2") (pinfunction "P_2") (pintype "passive"))
      (node (ref "SB16") (pin "1") (pinfunction "1_1") (pintype "passive"))
      (node (ref "U2") (pin "11") (pinfunction "VDDB_11") (pintype "power_in"))
    )
    (net (code "35") (name "Net-(C46-N)") (class "Default")
      (node (ref "C43") (pin "2") (pinfunction "2_2") (pintype "passive"))
      (node (ref "C44") (pin "2") (pinfunction "2_2") (pintype "passive"))
      (node (ref "C46") (pin "1") (pinfunction "N_1") (pintype "passive"))
      (node (ref "C47") (pin "2") (pinfunction "2_2") (pintype "passive"))
      (node (ref "C48") (pin "2") (pinfunction "2_2") (pintype "passive"))
      (node (ref "C49") (pin "1") (pinfunction "N_1") (pintype "passive"))
      (node (ref "SB17") (pin "1") (pinfunction "1_1") (pintype "passive"))
      (node (ref "SB18") (pin "2") (pinfunction "2_2") (pintype "passive"))
      (node (ref "SB19") (pin "2") (pinfunction "2_2") (pintype "passive"))
      (node (ref "U2") (pin "9") (pinfunction "VSSB_9") (pintype "power_in"))
    )
    (net (code "36") (name "Net-(C54-P)") (class "Default")
      (node (ref "C53") (pin "1") (pinfunction "1_1") (pintype "passive"))
      (node (ref "C54") (pin "2") (pinfunction "P_2") (pintype "passive"))
      (node (ref "SB23") (pin "1") (pinfunction "1_1") (pintype "passive"))
      (node (ref "SB24") (pin "1") (pinfunction "1_1") (pintype "passive"))
      (node (ref "U3") (pin "3") (pinfunction "VCCI_3") (pintype "power_in"))
      (node (ref "U3") (pin "8") (pinfunction "VCCI_8") (pintype "power_in"))
    )
    (net (code "37") (name "Net-(C58-N)") (class "Default")
      (node (ref "C55") (pin "2") (pinfunction "2_2") (pintype "passive"))
      (node (ref "C56") (pin "2") (pinfunction "2_2") (pintype "passive"))
      (node (ref "C57") (pin "2") (pinfunction "2_2") (pintype "passive"))
      (node (ref "C58") (pin "1") (pinfunction "N_1") (pintype "passive"))
      (node (ref "C60") (pin "1") (pinfunction "1_1") (pintype "passive"))
      (node (ref "C62") (pin "1") (pinfunction "1_1") (pintype "passive"))
      (node (ref "C63") (pin "1") (pinfunction "1_1") (pintype "passive"))
      (node (ref "C64") (pin "2") (pinfunction "P_2") (pintype "passive"))
      (node (ref "SB26") (pin "1") (pinfunction "1_1") (pintype "passive"))
    )
    (net (code "38") (name "Net-(C58-P)") (class "Default")
      (node (ref "C55") (pin "1") (pinfunction "1_1") (pintype "passive"))
      (node (ref "C56") (pin "1") (pinfunction "1_1") (pintype "passive"))
      (node (ref "C57") (pin "1") (pinfunction "1_1") (pintype "passive"))
      (node (ref "C58") (pin "2") (pinfunction "P_2") (pintype "passive"))
      (node (ref "C59") (pin "1") (pinfunction "1_1") (pintype "passive"))
      (node (ref "C61") (pin "2") (pinfunction "P_2") (pintype "passive"))
      (node (ref "D13") (pin "2") (pinfunction "K_2") (pintype "passive"))
      (node (ref "SB27") (pin "1") (pinfunction "1_1") (pintype "passive"))
      (node (ref "U3") (pin "16") (pinfunction "VDDA_16") (pintype "power_in"))
    )
    (net (code "39") (name "Net-(C61-N)") (class "Default")
      (node (ref "C59") (pin "2") (pinfunction "2_2") (pintype "passive"))
      (node (ref "C60") (pin "2") (pinfunction "2_2") (pintype "passive"))
      (node (ref "C61") (pin "1") (pinfunction "N_1") (pintype "passive"))
      (node (ref "C62") (pin "2") (pinfunction "2_2") (pintype "passive"))
      (node (ref "C63") (pin "2") (pinfunction "2_2") (pintype "passive"))
      (node (ref "C64") (pin "1") (pinfunction "N_1") (pintype "passive"))
      (node (ref "SB22") (pin "1") (pinfunction "1_1") (pintype "passive"))
      (node (ref "SB28") (pin "1") (pinfunction "1_1") (pintype "passive"))
      (node (ref "SB30") (pin "1") (pinfunction "1_1") (pintype "passive"))
      (node (ref "U3") (pin "14") (pinfunction "VSSA_14") (pintype "power_in"))
    )
    (net (code "40") (name "Net-(C70-N)") (class "Default")
      (node (ref "C65") (pin "2") (pinfunction "2_2") (pintype "passive"))
      (node (ref "C68") (pin "2") (pinfunction "2_2") (pintype "passive"))
      (node (ref "C69") (pin "2") (pinfunction "2_2") (pintype "passive"))
      (node (ref "C70") (pin "1") (pinfunction "N_1") (pintype "passive"))
      (node (ref "C72") (pin "1") (pinfunction "1_1") (pintype "passive"))
      (node (ref "C75") (pin "1") (pinfunction "1_1") (pintype "passive"))
      (node (ref "C76") (pin "1") (pinfunction "1_1") (pintype "passive"))
      (node (ref "C77") (pin "2") (pinfunction "P_2") (pintype "passive"))
      (node (ref "SB34") (pin "2") (pinfunction "2_2") (pintype "passive"))
    )
    (net (code "41") (name "Net-(C70-P)") (class "Default")
      (node (ref "C65") (pin "1") (pinfunction "1_1") (pintype "passive"))
      (node (ref "C68") (pin "1") (pinfunction "1_1") (pintype "passive"))
      (node (ref "C69") (pin "1") (pinfunction "1_1") (pintype "passive"))
      (node (ref "C70") (pin "2") (pinfunction "P_2") (pintype "passive"))
      (node (ref "C71") (pin "1") (pinfunction "1_1") (pintype "passive"))
      (node (ref "C74") (pin "2") (pinfunction "P_2") (pintype "passive"))
      (node (ref "SB31") (pin "1") (pinfunction "1_1") (pintype "passive"))
      (node (ref "U3") (pin "11") (pinfunction "VDDB_11") (pintype "power_in"))
    )
    (net (code "42") (name "Net-(C74-N)") (class "Default")
      (node (ref "C71") (pin "2") (pinfunction "2_2") (pintype "passive"))
      (node (ref "C72") (pin "2") (pinfunction "2_2") (pintype "passive"))
      (node (ref "C74") (pin "1") (pinfunction "N_1") (pintype "passive"))
      (node (ref "C75") (pin "2") (pinfunction "2_2") (pintype "passive"))
      (node (ref "C76") (pin "2") (pinfunction "2_2") (pintype "passive"))
      (node (ref "C77") (pin "1") (pinfunction "N_1") (pintype "passive"))
      (node (ref "SB32") (pin "1") (pinfunction "1_1") (pintype "passive"))
      (node (ref "SB33") (pin "2") (pinfunction "2_2") (pintype "passive"))
      (node (ref "SB36") (pin "2") (pinfunction "2_2") (pintype "passive"))
      (node (ref "U3") (pin "9") (pinfunction "VSSB_9") (pintype "power_in"))
    )
    (net (code "43") (name "Net-(D12-A)") (class "Default")
      (node (ref "D12") (pin "1") (pinfunction "A_1") (pintype "passive"))
      (node (ref "SB13") (pin "2") (pinfunction "2_2") (pintype "passive"))
    )
    (net (code "44") (name "Net-(D13-A)") (class "Default")
      (node (ref "D13") (pin "1") (pinfunction "A_1") (pintype "passive"))
      (node (ref "SB29") (pin "2") (pinfunction "2_2") (pintype "passive"))
    )
    (net (code "45") (name "Net-(U2-DT)") (class "Default")
      (node (ref "C52") (pin "1") (pinfunction "1_1") (pintype "passive"))
      (node (ref "R37") (pin "2") (pinfunction "2_2") (pintype "passive"))
      (node (ref "R38") (pin "2") (pinfunction "2_2") (pintype "passive"))
      (node (ref "U2") (pin "6") (pinfunction "DT_6") (pintype "bidirectional"))
    )
    (net (code "46") (name "Net-(U2-INA)") (class "Default")
      (node (ref "C38") (pin "1") (pinfunction "1_1") (pintype "passive"))
      (node (ref "R32") (pin "2") (pinfunction "2_2") (pintype "passive"))
      (node (ref "U2") (pin "1") (pinfunction "INA_1") (pintype "bidirectional"))
    )
    (net (code "47") (name "Net-(U2-INB)") (class "Default")
      (node (ref "C39") (pin "1") (pinfunction "1_1") (pintype "passive"))
      (node (ref "R33") (pin "2") (pinfunction "2_2") (pintype "passive"))
      (node (ref "U2") (pin "2") (pinfunction "INB_2") (pintype "bidirectional"))
    )
    (net (code "48") (name "Net-(U3-DT)") (class "Default")
      (node (ref "C78") (pin "1") (pinfunction "1_1") (pintype "passive"))
      (node (ref "R42") (pin "2") (pinfunction "2_2") (pintype "passive"))
      (node (ref "R43") (pin "2") (pinfunction "2_2") (pintype "passive"))
      (node (ref "U3") (pin "6") (pinfunction "DT_6") (pintype "bidirectional"))
    )
    (net (code "49") (name "Net-(U3-INA)") (class "Default")
      (node (ref "C66") (pin "1") (pinfunction "1_1") (pintype "passive"))
      (node (ref "R39") (pin "2") (pinfunction "2_2") (pintype "passive"))
      (node (ref "U3") (pin "1") (pinfunction "INA_1") (pintype "bidirectional"))
    )
    (net (code "50") (name "Net-(U3-INB)") (class "Default")
      (node (ref "C67") (pin "1") (pinfunction "1_1") (pintype "passive"))
      (node (ref "R40") (pin "2") (pinfunction "2_2") (pintype "passive"))
      (node (ref "U3") (pin "2") (pinfunction "INB_2") (pintype "bidirectional"))
    )
    (net (code "51") (name "Net-(VR1-Adj)") (class "Default")
      (node (ref "R30") (pin "2") (pinfunction "2_2") (pintype "passive"))
      (node (ref "VR1") (pin "1") (pinfunction "Adj_1") (pintype "passive"))
    )
    (net (code "52") (name "Net-(VR2-Adj)") (class "Default")
      (node (ref "R35") (pin "2") (pinfunction "2_2") (pintype "passive"))
      (node (ref "VR2") (pin "1") (pinfunction "Adj_1") (pintype "passive"))
    )
  )
)
